# Power_Supply.net
KiCad netlist of a schematic drawn in Altium Designer
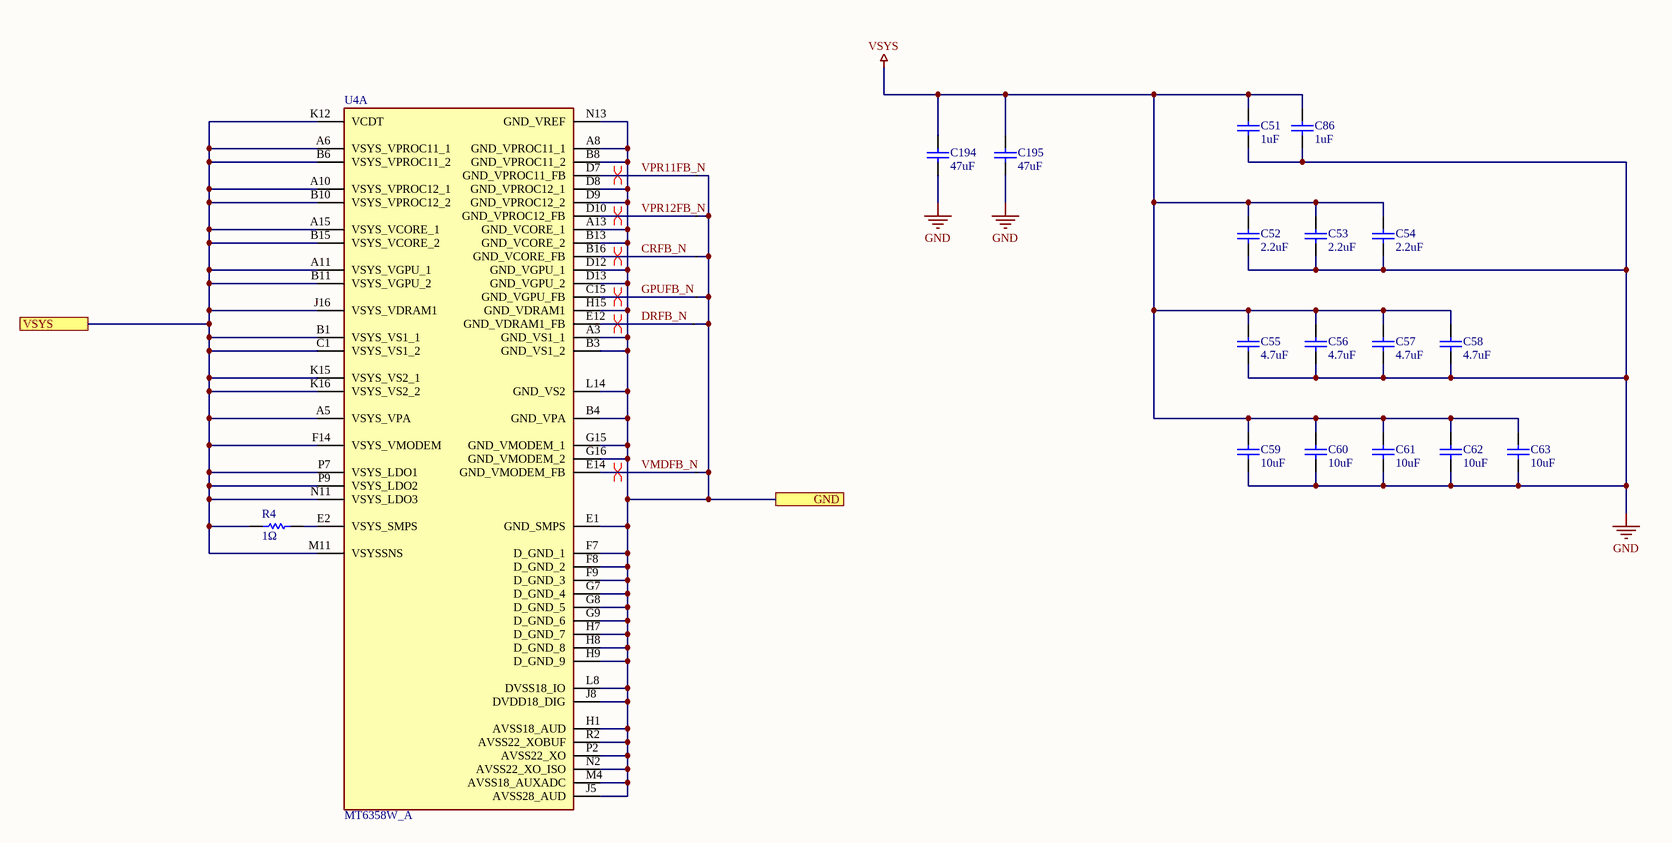
[diagram p0: Power_Supply.SchDoc]

(export (version "E")
  (design (tool "Eeschema 10.0.6"))
  (components
    (comp (ref ".1") (value "P") (footprint "P") (libsource (lib "kit") (part "P")))
    (comp (ref ".2") (value "P") (footprint "P") (libsource (lib "kit") (part "P")))
    (comp (ref ".3") (value "P") (footprint "P") (libsource (lib "kit") (part "P")))
    (comp (ref ".4") (value "P") (footprint "P") (libsource (lib "kit") (part "P")))
    (comp (ref ".5") (value "P") (footprint "P") (libsource (lib "kit") (part "P")))
    (comp (ref ".8") (value "P") (footprint "P") (libsource (lib "kit") (part "P")))
    (comp (ref "C51")
      (value "1uF")
      (footprint "C0805")
      (fields (field (name "Comment") "C0805"))
      (libsource (lib "kit") (part "C0805"))
    )
    (comp (ref "C52")
      (value "2.2uF")
      (footprint "C0805")
      (fields (field (name "Comment") "C0805"))
      (libsource (lib "kit") (part "C0805"))
    )
    (comp (ref "C53")
      (value "2.2uF")
      (footprint "C0805")
      (fields (field (name "Comment") "C0805"))
      (libsource (lib "kit") (part "C0805"))
    )
    (comp (ref "C54")
      (value "2.2uF")
      (footprint "C0805")
      (fields (field (name "Comment") "C0805"))
      (libsource (lib "kit") (part "C0805"))
    )
    (comp (ref "C55")
      (value "4.7uF")
      (footprint "C0805")
      (fields (field (name "Comment") "C0805"))
      (libsource (lib "kit") (part "C0805"))
    )
    (comp (ref "C56")
      (value "4.7uF")
      (footprint "C0805")
      (fields (field (name "Comment") "C0805"))
      (libsource (lib "kit") (part "C0805"))
    )
    (comp (ref "C57")
      (value "4.7uF")
      (footprint "C0805")
      (fields (field (name "Comment") "C0805"))
      (libsource (lib "kit") (part "C0805"))
    )
    (comp (ref "C58")
      (value "4.7uF")
      (footprint "C0805")
      (fields (field (name "Comment") "C0805"))
      (libsource (lib "kit") (part "C0805"))
    )
    (comp (ref "C59")
      (value "10uF")
      (footprint "C1210")
      (fields (field (name "Comment") "C1210"))
      (libsource (lib "kit") (part "C1210"))
    )
    (comp (ref "C60")
      (value "10uF")
      (footprint "C1210")
      (fields (field (name "Comment") "C1210"))
      (libsource (lib "kit") (part "C1210"))
    )
    (comp (ref "C61")
      (value "10uF")
      (footprint "C1210")
      (fields (field (name "Comment") "C1210"))
      (libsource (lib "kit") (part "C1210"))
    )
    (comp (ref "C62")
      (value "10uF")
      (footprint "C1210")
      (fields (field (name "Comment") "C1210"))
      (libsource (lib "kit") (part "C1210"))
    )
    (comp (ref "C63")
      (value "10uF")
      (footprint "C1210")
      (fields (field (name "Comment") "C1210"))
      (libsource (lib "kit") (part "C1210"))
    )
    (comp (ref "C86")
      (value "1uF")
      (footprint "C0805")
      (fields (field (name "Comment") "C0805"))
      (libsource (lib "kit") (part "C0805"))
    )
    (comp (ref "C194")
      (value "47uF")
      (footprint "C1812")
      (fields (field (name "Comment") "C1812"))
      (libsource (lib "kit") (part "C1812"))
    )
    (comp (ref "C195")
      (value "47uF")
      (footprint "C1812")
      (fields (field (name "Comment") "C1812"))
      (libsource (lib "kit") (part "C1812"))
    )
    (comp (ref "R4")
      (value "1Ω")
      (footprint "R0603")
      (fields (field (name "Comment") "R0603"))
      (libsource (lib "kit") (part "R0603"))
    )
    (comp (ref "U4")
      (value "MT6358W_A")
      (footprint "BGA194C40P16X15_640X600X66")
      (description "PMIC")
      (fields
        (field (name "MANUFACTURER_PART_NUMBER") "MT6358W/A")
        (field (name "MOUSER PART NUMBER") "840-MT6358W/A")
      )
      (libsource (lib "kit") (part "MT6358W_A"))
    )
  )
  (nets
    (net (code "1") (name "/CRFB_N") (class "Default")
      (node (ref ".3") (pin "1") (pinfunction "1_1") (pintype "passive"))
      (node (ref "U4") (pin "B16") (pinfunction "GND_VCORE_FB_B16") (pintype "passive"))
    )
    (net (code "2") (name "/DRFB_N") (class "Default")
      (node (ref ".8") (pin "1") (pinfunction "1_1") (pintype "passive"))
      (node (ref "U4") (pin "E12") (pinfunction "GND_VDRAM1_FB_E12") (pintype "passive"))
    )
    (net (code "3") (name "/GPUFB_N") (class "Default")
      (node (ref ".4") (pin "1") (pinfunction "1_1") (pintype "passive"))
      (node (ref "U4") (pin "C15") (pinfunction "GND_VGPU_FB_C15") (pintype "passive"))
    )
    (net (code "4") (name "/VMDFB_N") (class "Default")
      (node (ref ".5") (pin "1") (pinfunction "1_1") (pintype "passive"))
      (node (ref "U4") (pin "E14") (pinfunction "GND_VMODEM_FB_E14") (pintype "passive"))
    )
    (net (code "5") (name "/VPR11FB_N") (class "Default")
      (node (ref ".1") (pin "1") (pinfunction "1_1") (pintype "passive"))
      (node (ref "U4") (pin "D7") (pinfunction "GND_VPROC11_FB_D7") (pintype "passive"))
    )
    (net (code "6") (name "/VPR12FB_N") (class "Default")
      (node (ref ".2") (pin "1") (pinfunction "1_1") (pintype "passive"))
      (node (ref "U4") (pin "D10") (pinfunction "GND_VPROC12_FB_D10") (pintype "passive"))
    )
    (net (code "7") (name "GND") (class "Default")
      (node (ref ".1") (pin "2") (pinfunction "2_2") (pintype "passive"))
      (node (ref ".2") (pin "2") (pinfunction "2_2") (pintype "passive"))
      (node (ref ".3") (pin "2") (pinfunction "2_2") (pintype "passive"))
      (node (ref ".4") (pin "2") (pinfunction "2_2") (pintype "passive"))
      (node (ref ".5") (pin "2") (pinfunction "2_2") (pintype "passive"))
      (node (ref ".8") (pin "2") (pinfunction "2_2") (pintype "passive"))
      (node (ref "C194") (pin "1") (pinfunction "1_1") (pintype "passive"))
      (node (ref "C195") (pin "1") (pinfunction "1_1") (pintype "passive"))
      (node (ref "C51") (pin "1") (pinfunction "1_1") (pintype "passive"))
      (node (ref "C52") (pin "1") (pinfunction "1_1") (pintype "passive"))
      (node (ref "C53") (pin "1") (pinfunction "1_1") (pintype "passive"))
      (node (ref "C54") (pin "1") (pinfunction "1_1") (pintype "passive"))
      (node (ref "C55") (pin "1") (pinfunction "1_1") (pintype "passive"))
      (node (ref "C56") (pin "1") (pinfunction "1_1") (pintype "passive"))
      (node (ref "C57") (pin "1") (pinfunction "1_1") (pintype "passive"))
      (node (ref "C58") (pin "1") (pinfunction "1_1") (pintype "passive"))
      (node (ref "C59") (pin "1") (pinfunction "1_1") (pintype "passive"))
      (node (ref "C60") (pin "1") (pinfunction "1_1") (pintype "passive"))
      (node (ref "C61") (pin "1") (pinfunction "1_1") (pintype "passive"))
      (node (ref "C62") (pin "1") (pinfunction "1_1") (pintype "passive"))
      (node (ref "C63") (pin "1") (pinfunction "1_1") (pintype "passive"))
      (node (ref "C86") (pin "1") (pinfunction "1_1") (pintype "passive"))
      (node (ref "U4") (pin "A13") (pinfunction "GND_VCORE_1_A13") (pintype "passive"))
      (node (ref "U4") (pin "A3") (pinfunction "GND_VS1_1_A3") (pintype "passive"))
      (node (ref "U4") (pin "A8") (pinfunction "GND_VPROC11_1_A8") (pintype "passive"))
      (node (ref "U4") (pin "B13") (pinfunction "GND_VCORE_2_B13") (pintype "passive"))
      (node (ref "U4") (pin "B3") (pinfunction "GND_VS1_2_B3") (pintype "passive"))
      (node (ref "U4") (pin "B4") (pinfunction "GND_VPA_B4") (pintype "passive"))
      (node (ref "U4") (pin "B8") (pinfunction "GND_VPROC11_2_B8") (pintype "passive"))
      (node (ref "U4") (pin "D12") (pinfunction "GND_VGPU_1_D12") (pintype "passive"))
      (node (ref "U4") (pin "D13") (pinfunction "GND_VGPU_2_D13") (pintype "passive"))
      (node (ref "U4") (pin "D8") (pinfunction "GND_VPROC12_1_D8") (pintype "passive"))
      (node (ref "U4") (pin "D9") (pinfunction "GND_VPROC12_2_D9") (pintype "passive"))
      (node (ref "U4") (pin "E1") (pinfunction "GND_SMPS_E1") (pintype "passive"))
      (node (ref "U4") (pin "F7") (pinfunction "D_GND_1_F7") (pintype "passive"))
      (node (ref "U4") (pin "F8") (pinfunction "D_GND_2_F8") (pintype "passive"))
      (node (ref "U4") (pin "F9") (pinfunction "D_GND_3_F9") (pintype "passive"))
      (node (ref "U4") (pin "G15") (pinfunction "GND_VMODEM_1_G15") (pintype "passive"))
      (node (ref "U4") (pin "G16") (pinfunction "GND_VMODEM_2_G16") (pintype "passive"))
      (node (ref "U4") (pin "G7") (pinfunction "D_GND_4_G7") (pintype "passive"))
      (node (ref "U4") (pin "G8") (pinfunction "D_GND_5_G8") (pintype "passive"))
      (node (ref "U4") (pin "G9") (pinfunction "D_GND_6_G9") (pintype "passive"))
      (node (ref "U4") (pin "H1") (pinfunction "AVSS18_AUD_H1") (pintype "passive"))
      (node (ref "U4") (pin "H15") (pinfunction "GND_VDRAM1_H15") (pintype "passive"))
      (node (ref "U4") (pin "H7") (pinfunction "D_GND_7_H7") (pintype "passive"))
      (node (ref "U4") (pin "H8") (pinfunction "D_GND_8_H8") (pintype "passive"))
      (node (ref "U4") (pin "H9") (pinfunction "D_GND_9_H9") (pintype "passive"))
      (node (ref "U4") (pin "J5") (pinfunction "AVSS28_AUD_J5") (pintype "passive"))
      (node (ref "U4") (pin "J8") (pinfunction "DVDD18_DIG_J8") (pintype "passive"))
      (node (ref "U4") (pin "L14") (pinfunction "GND_VS2_L14") (pintype "passive"))
      (node (ref "U4") (pin "L8") (pinfunction "DVSS18_IO_L8") (pintype "passive"))
      (node (ref "U4") (pin "M4") (pinfunction "AVSS18_AUXADC_M4") (pintype "passive"))
      (node (ref "U4") (pin "N13") (pinfunction "GND_VREF_N13") (pintype "passive"))
      (node (ref "U4") (pin "N2") (pinfunction "AVSS22_XO_ISO_N2") (pintype "passive"))
      (node (ref "U4") (pin "P2") (pinfunction "AVSS22_XO_P2") (pintype "passive"))
      (node (ref "U4") (pin "R2") (pinfunction "AVSS22_XOBUF_R2") (pintype "passive"))
    )
    (net (code "8") (name "Net-(U4A-VSYS_SMPS)") (class "Default")
      (node (ref "R4") (pin "2") (pinfunction "2_2") (pintype "passive"))
      (node (ref "U4") (pin "E2") (pinfunction "VSYS_SMPS_E2") (pintype "passive"))
    )
    (net (code "9") (name "VSYS") (class "Default")
      (node (ref "C194") (pin "2") (pinfunction "2_2") (pintype "passive"))
      (node (ref "C195") (pin "2") (pinfunction "2_2") (pintype "passive"))
      (node (ref "C51") (pin "2") (pinfunction "2_2") (pintype "passive"))
      (node (ref "C52") (pin "2") (pinfunction "2_2") (pintype "passive"))
      (node (ref "C53") (pin "2") (pinfunction "2_2") (pintype "passive"))
      (node (ref "C54") (pin "2") (pinfunction "2_2") (pintype "passive"))
      (node (ref "C55") (pin "2") (pinfunction "2_2") (pintype "passive"))
      (node (ref "C56") (pin "2") (pinfunction "2_2") (pintype "passive"))
      (node (ref "C57") (pin "2") (pinfunction "2_2") (pintype "passive"))
      (node (ref "C58") (pin "2") (pinfunction "2_2") (pintype "passive"))
      (node (ref "C59") (pin "2") (pinfunction "2_2") (pintype "passive"))
      (node (ref "C60") (pin "2") (pinfunction "2_2") (pintype "passive"))
      (node (ref "C61") (pin "2") (pinfunction "2_2") (pintype "passive"))
      (node (ref "C62") (pin "2") (pinfunction "2_2") (pintype "passive"))
      (node (ref "C63") (pin "2") (pinfunction "2_2") (pintype "passive"))
      (node (ref "C86") (pin "2") (pinfunction "2_2") (pintype "passive"))
      (node (ref "R4") (pin "1") (pinfunction "1_1") (pintype "passive"))
      (node (ref "U4") (pin "A10") (pinfunction "VSYS_VPROC12_1_A10") (pintype "passive"))
      (node (ref "U4") (pin "A11") (pinfunction "VSYS_VGPU_1_A11") (pintype "passive"))
      (node (ref "U4") (pin "A15") (pinfunction "VSYS_VCORE_1_A15") (pintype "passive"))
      (node (ref "U4") (pin "A5") (pinfunction "VSYS_VPA_A5") (pintype "passive"))
      (node (ref "U4") (pin "A6") (pinfunction "VSYS_VPROC11_1_A6") (pintype "passive"))
      (node (ref "U4") (pin "B1") (pinfunction "VSYS_VS1_1_B1") (pintype "passive"))
      (node (ref "U4") (pin "B10") (pinfunction "VSYS_VPROC12_2_B10") (pintype "passive"))
      (node (ref "U4") (pin "B11") (pinfunction "VSYS_VGPU_2_B11") (pintype "passive"))
      (node (ref "U4") (pin "B15") (pinfunction "VSYS_VCORE_2_B15") (pintype "passive"))
      (node (ref "U4") (pin "B6") (pinfunction "VSYS_VPROC11_2_B6") (pintype "passive"))
      (node (ref "U4") (pin "C1") (pinfunction "VSYS_VS1_2_C1") (pintype "passive"))
      (node (ref "U4") (pin "F14") (pinfunction "VSYS_VMODEM_F14") (pintype "passive"))
      (node (ref "U4") (pin "J16") (pinfunction "VSYS_VDRAM1_J16") (pintype "passive"))
      (node (ref "U4") (pin "K12") (pinfunction "VCDT_K12") (pintype "passive"))
      (node (ref "U4") (pin "K15") (pinfunction "VSYS_VS2_1_K15") (pintype "passive"))
      (node (ref "U4") (pin "K16") (pinfunction "VSYS_VS2_2_K16") (pintype "passive"))
      (node (ref "U4") (pin "M11") (pinfunction "VSYSSNS_M11") (pintype "passive"))
      (node (ref "U4") (pin "N11") (pinfunction "VSYS_LDO3_N11") (pintype "passive"))
      (node (ref "U4") (pin "P7") (pinfunction "VSYS_LDO1_P7") (pintype "passive"))
      (node (ref "U4") (pin "P9") (pinfunction "VSYS_LDO2_P9") (pintype "passive"))
    )
  )
)
